# bodenfeuchte_1.net
KiCad netlist of a schematic drawn in EAGLE
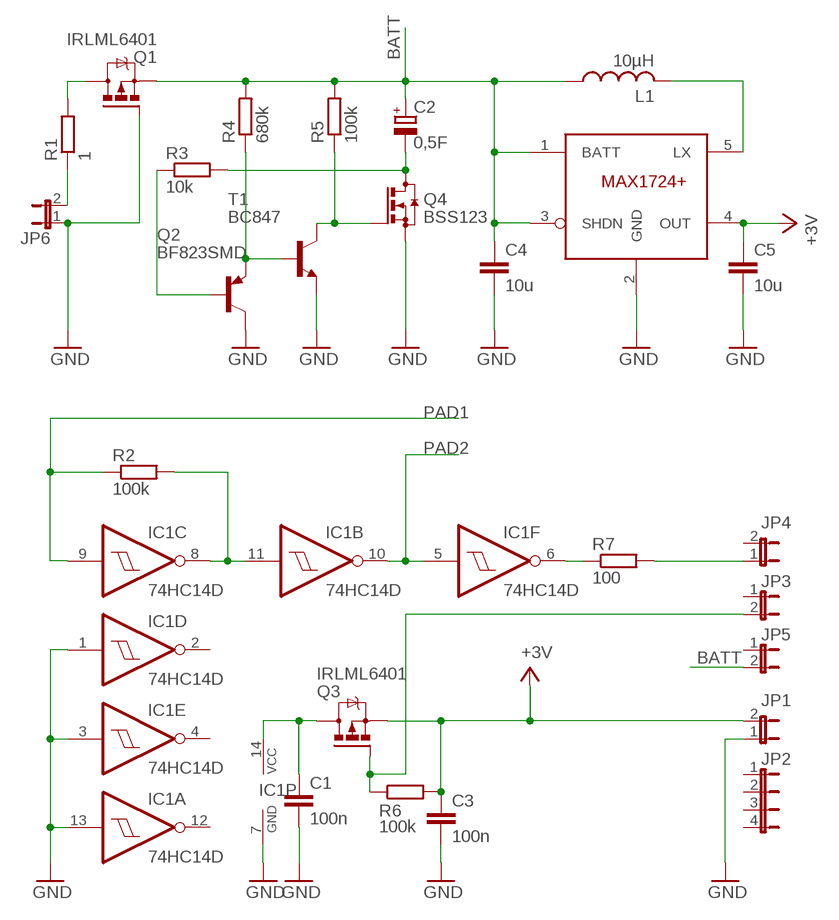
[diagram p0: schematic, sheet 1]

(export (version "E")
  (design (tool "Eeschema 10.0.6"))
  (components
    (comp (ref "C1")
      (value "100n")
      (footprint "eagle-import:C0805")
      (libsource (lib "eagle-import") (part "resistor_C-EUC0805"))
    )
    (comp (ref "C2")
      (value "0,5F")
      (footprint "eagle-import:GOLDCAP5-21.5")
      (libsource (lib "eagle-import") (part "CPOL-EUTAP5-80"))
    )
    (comp (ref "C3")
      (value "100n")
      (footprint "eagle-import:C0805")
      (libsource (lib "eagle-import") (part "resistor_C-EUC0805"))
    )
    (comp (ref "C4")
      (value "10u")
      (footprint "eagle-import:C0805")
      (libsource (lib "eagle-import") (part "C-EUC0805"))
    )
    (comp (ref "C5")
      (value "10u")
      (footprint "eagle-import:C0805")
      (libsource (lib "eagle-import") (part "C-EUC0805"))
    )
    (comp (ref "IC1")
      (value "74HC14D")
      (footprint "eagle-import:SO14")
      (libsource (lib "eagle-import") (part "7414DHC"))
    )
    (comp (ref "JP1")
      (value "JP1E")
      (footprint "eagle-import:JP1")
      (libsource (lib "eagle-import") (part "JP1E"))
    )
    (comp (ref "JP2")
      (value "JP4E")
      (footprint "eagle-import:JP4")
      (libsource (lib "eagle-import") (part "JP4E"))
    )
    (comp (ref "JP3")
      (value "JP1E")
      (footprint "eagle-import:JP1")
      (libsource (lib "eagle-import") (part "JP1E"))
    )
    (comp (ref "JP4")
      (value "JP1E")
      (footprint "eagle-import:JP1")
      (libsource (lib "eagle-import") (part "JP1E"))
    )
    (comp (ref "JP5")
      (value "JP1E")
      (footprint "eagle-import:JP1")
      (libsource (lib "eagle-import") (part "JP1E"))
    )
    (comp (ref "JP6")
      (value "JP1E")
      (footprint "eagle-import:JP1")
      (libsource (lib "eagle-import") (part "JP1E"))
    )
    (comp (ref "L1")
      (value "10µH")
      (footprint "eagle-import:L1812")
      (libsource (lib "eagle-import") (part "L-USL1812"))
    )
    (comp (ref "Q1")
      (value "IRLML6401")
      (footprint "eagle-import:MICRO3")
      (libsource (lib "eagle-import") (part "IRLML5203"))
    )
    (comp (ref "Q2")
      (value "BF823SMD")
      (footprint "eagle-import:SOT23-BEC")
      (libsource (lib "eagle-import") (part "BF823SMD"))
    )
    (comp (ref "Q3")
      (value "IRLML6401")
      (footprint "eagle-import:MICRO3")
      (libsource (lib "eagle-import") (part "IRLML5203"))
    )
    (comp (ref "Q4")
      (value "BSS123")
      (footprint "eagle-import:SOT23")
      (libsource (lib "eagle-import") (part "BSS123"))
    )
    (comp (ref "R1")
      (value "1")
      (footprint "eagle-import:R0805")
      (libsource (lib "eagle-import") (part "R-EU_R0805"))
    )
    (comp (ref "R2")
      (value "100k")
      (footprint "eagle-import:R0805")
      (libsource (lib "eagle-import") (part "R-EU_R0805"))
    )
    (comp (ref "R3")
      (value "10k")
      (footprint "eagle-import:R0805")
      (libsource (lib "eagle-import") (part "R-EU_R0805"))
    )
    (comp (ref "R4")
      (value "680k")
      (footprint "eagle-import:R0805")
      (libsource (lib "eagle-import") (part "R-EU_R0805"))
    )
    (comp (ref "R5")
      (value "100k")
      (footprint "eagle-import:R0805")
      (libsource (lib "eagle-import") (part "R-EU_R0805"))
    )
    (comp (ref "R6")
      (value "100k")
      (footprint "eagle-import:R0805")
      (libsource (lib "eagle-import") (part "R-EU_R0805"))
    )
    (comp (ref "R7")
      (value "100")
      (footprint "eagle-import:R0805")
      (libsource (lib "eagle-import") (part "R-EU_R0805"))
    )
    (comp (ref "T1")
      (value "BC847")
      (footprint "eagle-import:SOT23")
      (libsource (lib "eagle-import") (part "BC847"))
    )
    (comp (ref "U$1")
      (value "MAX1724")
      (footprint "eagle-import:SOT23-5L")
      (libsource (lib "eagle-import") (part "MAX1724"))
    )
  )
  (nets
    (net (code "1") (name "+3V") (class "Default")
      (node (ref "C3") (pin "1") (pinfunction "1_1") (pintype "passive"))
      (node (ref "C5") (pin "1") (pinfunction "1_1") (pintype "passive"))
      (node (ref "JP1") (pin "2") (pinfunction "2_2") (pintype "passive"))
      (node (ref "Q3") (pin "2") (pinfunction "S_2") (pintype "passive"))
      (node (ref "R6") (pin "2") (pinfunction "2_2") (pintype "passive"))
      (node (ref "U$1") (pin "4") (pinfunction "OUT_4") (pintype "output"))
    )
    (net (code "2") (name "/BATT") (class "Default")
      (node (ref "C2") (pin "+") (pinfunction "+_+") (pintype "passive"))
      (node (ref "C4") (pin "1") (pinfunction "1_1") (pintype "passive"))
      (node (ref "JP5") (pin "2") (pinfunction "2_2") (pintype "passive"))
      (node (ref "L1") (pin "1") (pinfunction "1_1") (pintype "passive"))
      (node (ref "Q1") (pin "2") (pinfunction "S_2") (pintype "passive"))
      (node (ref "R4") (pin "2") (pinfunction "2_2") (pintype "passive"))
      (node (ref "R5") (pin "2") (pinfunction "2_2") (pintype "passive"))
      (node (ref "U$1") (pin "1") (pinfunction "BATT_1") (pintype "power_in"))
      (node (ref "U$1") (pin "3") (pinfunction "SHDN_3") (pintype "bidirectional"))
    )
    (net (code "3") (name "/PAD1") (class "Default")
      (node (ref "IC1") (pin "9") (pinfunction "I_9") (pintype "input"))
      (node (ref "R2") (pin "1") (pinfunction "1_1") (pintype "passive"))
    )
    (net (code "4") (name "/PAD2") (class "Default")
      (node (ref "IC1") (pin "10") (pinfunction "O_10") (pintype "output"))
      (node (ref "IC1") (pin "5") (pinfunction "I_5") (pintype "input"))
    )
    (net (code "5") (name "GND") (class "Default")
      (node (ref "C1") (pin "2") (pinfunction "2_2") (pintype "passive"))
      (node (ref "C3") (pin "2") (pinfunction "2_2") (pintype "passive"))
      (node (ref "C4") (pin "2") (pinfunction "2_2") (pintype "passive"))
      (node (ref "C5") (pin "2") (pinfunction "2_2") (pintype "passive"))
      (node (ref "IC1") (pin "1") (pinfunction "I_1") (pintype "input"))
      (node (ref "IC1") (pin "13") (pinfunction "I_13") (pintype "input"))
      (node (ref "IC1") (pin "3") (pinfunction "I_3") (pintype "input"))
      (node (ref "IC1") (pin "7") (pinfunction "GND_7") (pintype "power_in"))
      (node (ref "JP1") (pin "1") (pinfunction "1_1") (pintype "passive"))
      (node (ref "JP6") (pin "1") (pinfunction "1_1") (pintype "passive"))
      (node (ref "Q1") (pin "1") (pinfunction "G_1") (pintype "passive"))
      (node (ref "Q2") (pin "C") (pinfunction "C_C") (pintype "passive"))
      (node (ref "Q4") (pin "2") (pinfunction "S_2") (pintype "passive"))
      (node (ref "T1") (pin "2") (pinfunction "E_2") (pintype "passive"))
      (node (ref "U$1") (pin "2") (pinfunction "GND_2") (pintype "power_in"))
    )
    (net (code "6") (name "Net-(IC1B-I)") (class "Default")
      (node (ref "IC1") (pin "11") (pinfunction "I_11") (pintype "input"))
      (node (ref "IC1") (pin "8") (pinfunction "O_8") (pintype "output"))
      (node (ref "R2") (pin "2") (pinfunction "2_2") (pintype "passive"))
    )
    (net (code "7") (name "Net-(IC1F-O)") (class "Default")
      (node (ref "IC1") (pin "6") (pinfunction "O_6") (pintype "output"))
      (node (ref "R7") (pin "1") (pinfunction "1_1") (pintype "passive"))
    )
    (net (code "8") (name "Net-(IC1G-VCC)") (class "Default")
      (node (ref "C1") (pin "1") (pinfunction "1_1") (pintype "passive"))
      (node (ref "IC1") (pin "14") (pinfunction "VCC_14") (pintype "power_in"))
      (node (ref "Q3") (pin "3") (pinfunction "D_3") (pintype "passive"))
    )
    (net (code "9") (name "Net-(JP4-Pad1)") (class "Default")
      (node (ref "JP4") (pin "1") (pinfunction "1_1") (pintype "passive"))
      (node (ref "R7") (pin "2") (pinfunction "2_2") (pintype "passive"))
    )
    (net (code "10") (name "Net-(JP6-Pad2)") (class "Default")
      (node (ref "JP6") (pin "2") (pinfunction "2_2") (pintype "passive"))
      (node (ref "R1") (pin "1") (pinfunction "1_1") (pintype "passive"))
    )
    (net (code "11") (name "Net-(Q1-D)") (class "Default")
      (node (ref "Q1") (pin "3") (pinfunction "D_3") (pintype "passive"))
      (node (ref "R1") (pin "2") (pinfunction "2_2") (pintype "passive"))
    )
    (net (code "12") (name "Net-(Q2-PadB)") (class "Default")
      (node (ref "Q2") (pin "B") (pinfunction "B_B") (pintype "passive"))
      (node (ref "R3") (pin "1") (pinfunction "1_1") (pintype "passive"))
    )
    (net (code "13") (name "Net-(Q3-G)") (class "Default")
      (node (ref "JP3") (pin "2") (pinfunction "2_2") (pintype "passive"))
      (node (ref "Q3") (pin "1") (pinfunction "G_1") (pintype "passive"))
      (node (ref "R6") (pin "1") (pinfunction "1_1") (pintype "passive"))
    )
    (net (code "14") (name "Net-(Q4-D)") (class "Default")
      (node (ref "C2") (pin "-") (pinfunction "-_-") (pintype "passive"))
      (node (ref "Q4") (pin "3") (pinfunction "D_3") (pintype "passive"))
      (node (ref "R3") (pin "2") (pinfunction "2_2") (pintype "passive"))
    )
    (net (code "15") (name "Net-(Q4-G)") (class "Default")
      (node (ref "Q4") (pin "1") (pinfunction "G_1") (pintype "passive"))
      (node (ref "R5") (pin "1") (pinfunction "1_1") (pintype "passive"))
      (node (ref "T1") (pin "3") (pinfunction "C_3") (pintype "passive"))
    )
    (net (code "16") (name "Net-(T1-B)") (class "Default")
      (node (ref "Q2") (pin "E") (pinfunction "E_E") (pintype "passive"))
      (node (ref "R4") (pin "1") (pinfunction "1_1") (pintype "passive"))
      (node (ref "T1") (pin "1") (pinfunction "B_1") (pintype "passive"))
    )
    (net (code "17") (name "Net-(U$1-LX)") (class "Default")
      (node (ref "L1") (pin "2") (pinfunction "2_2") (pintype "passive"))
      (node (ref "U$1") (pin "5") (pinfunction "LX_5") (pintype "input"))
    )
    (net (code "18") (name "unconnected-(IC1A-O-Pad12)") (class "Default")
      (node (ref "IC1") (pin "12") (pinfunction "O_12") (pintype "output"))
    )
    (net (code "19") (name "unconnected-(IC1D-O-Pad2)") (class "Default")
      (node (ref "IC1") (pin "2") (pinfunction "O_2") (pintype "output"))
    )
    (net (code "20") (name "unconnected-(IC1E-O-Pad4)") (class "Default")
      (node (ref "IC1") (pin "4") (pinfunction "O_4") (pintype "output"))
    )
    (net (code "21") (name "unconnected-(JP2-Pad1)") (class "Default")
      (node (ref "JP2") (pin "1") (pinfunction "1_1") (pintype "passive"))
    )
    (net (code "22") (name "unconnected-(JP2-Pad2)") (class "Default")
      (node (ref "JP2") (pin "2") (pinfunction "2_2") (pintype "passive"))
    )
    (net (code "23") (name "unconnected-(JP2-Pad3)") (class "Default")
      (node (ref "JP2") (pin "3") (pinfunction "3_3") (pintype "passive"))
    )
    (net (code "24") (name "unconnected-(JP2-Pad4)") (class "Default")
      (node (ref "JP2") (pin "4") (pinfunction "4_4") (pintype "passive"))
    )
    (net (code "25") (name "unconnected-(JP3-Pad1)") (class "Default")
      (node (ref "JP3") (pin "1") (pinfunction "1_1") (pintype "passive"))
    )
    (net (code "26") (name "unconnected-(JP4-Pad2)") (class "Default")
      (node (ref "JP4") (pin "2") (pinfunction "2_2") (pintype "passive"))
    )
    (net (code "27") (name "unconnected-(JP5-Pad1)") (class "Default")
      (node (ref "JP5") (pin "1") (pinfunction "1_1") (pintype "passive"))
    )
  )
)
